# sketch_v1_01.net
KiCad netlist of a schematic drawn in EAGLE
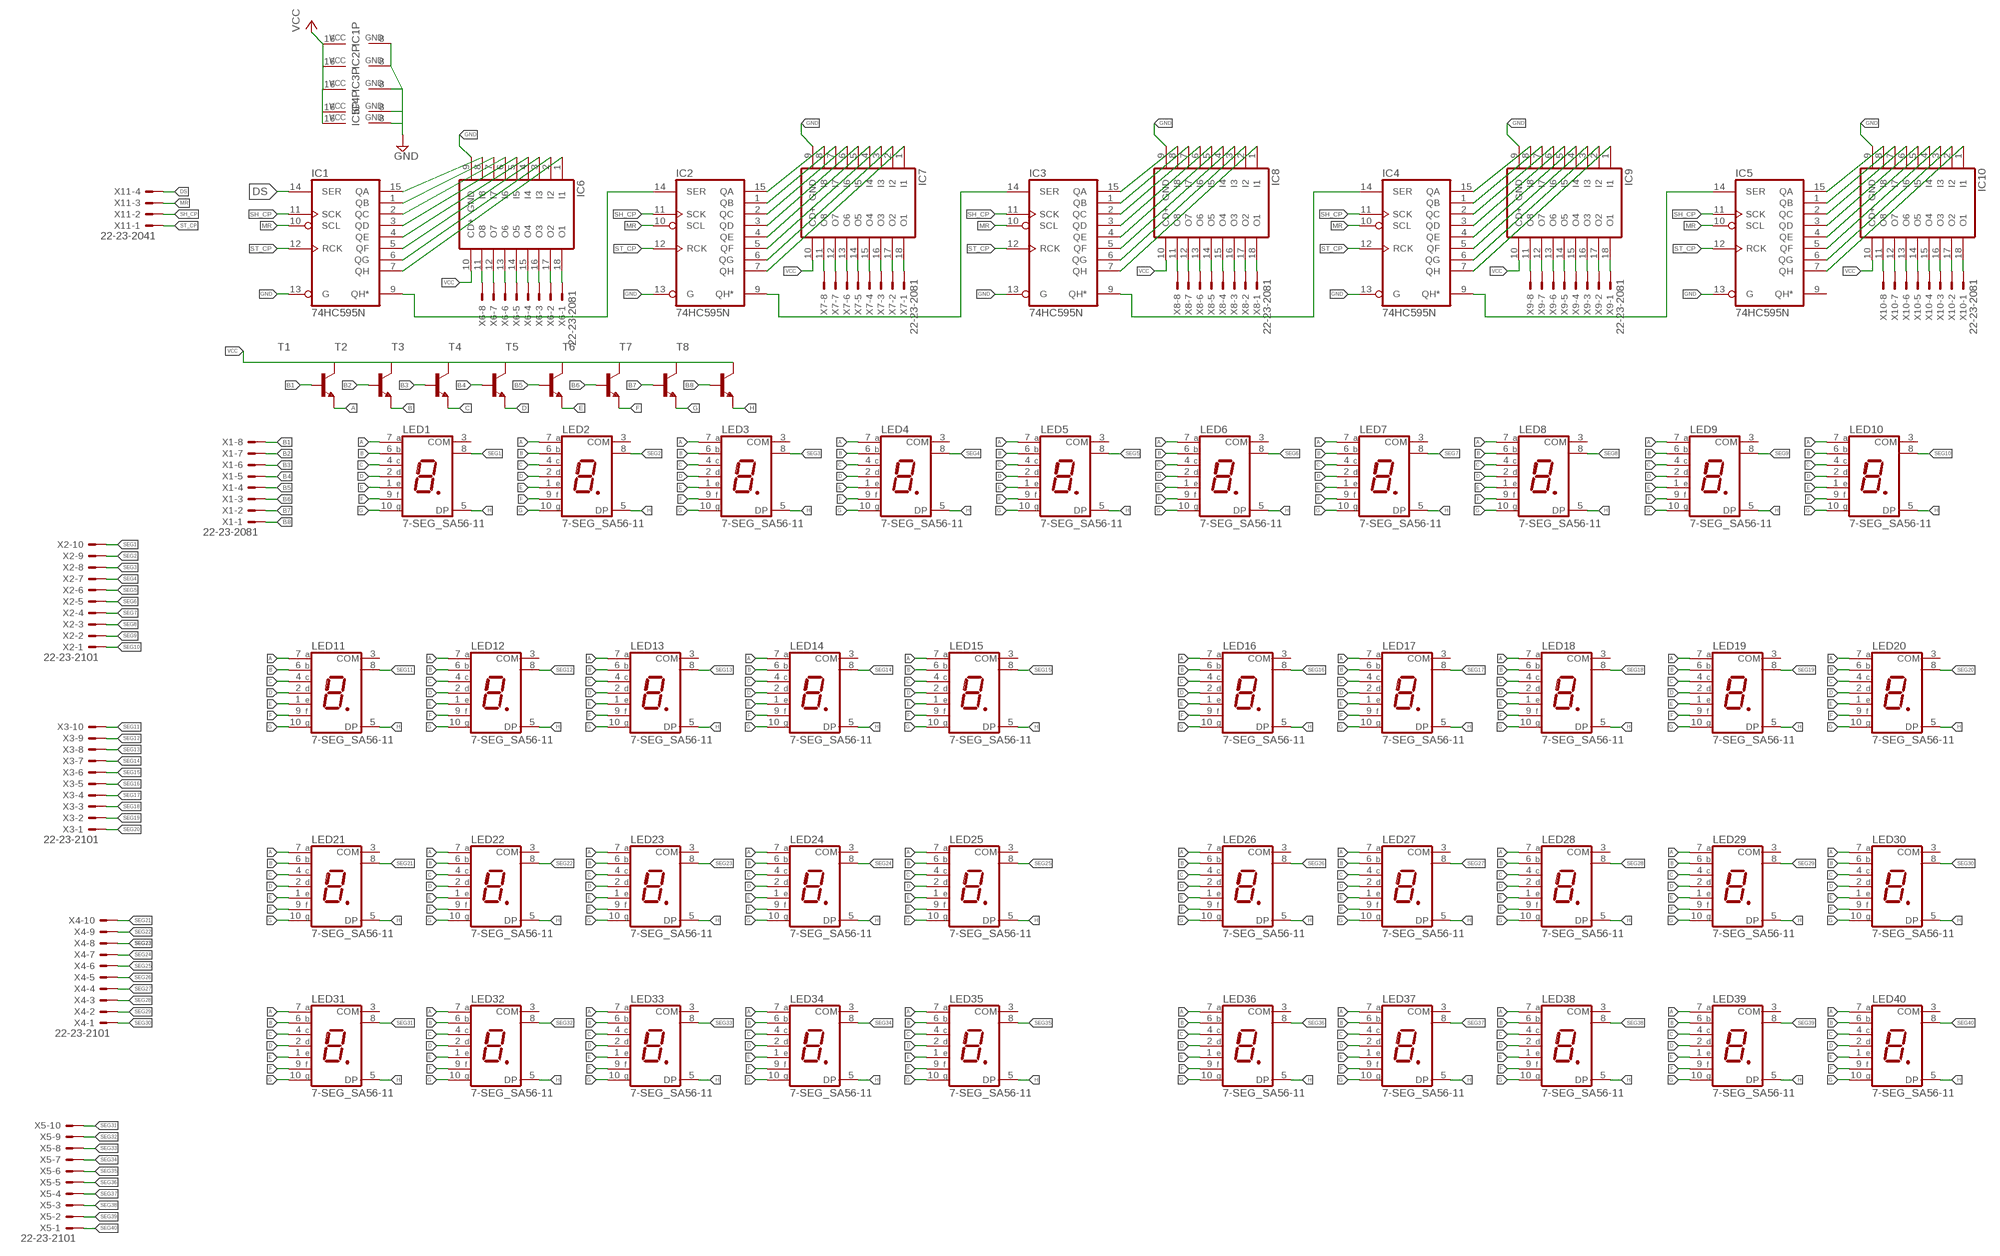
[diagram p0: schematic, sheet 1]

(export (version "E")
  (design (tool "Eeschema 10.0.6"))
  (components
    (comp (ref "IC1")
      (value "74HC595N")
      (footprint "eagle-import:DIL16")
      (libsource (lib "eagle-import") (part "74595NHC"))
    )
    (comp (ref "IC2")
      (value "74HC595N")
      (footprint "eagle-import:DIL16")
      (libsource (lib "eagle-import") (part "74595NHC"))
    )
    (comp (ref "IC3")
      (value "74HC595N")
      (footprint "eagle-import:DIL16")
      (libsource (lib "eagle-import") (part "74595NHC"))
    )
    (comp (ref "IC4")
      (value "74HC595N")
      (footprint "eagle-import:DIL16")
      (libsource (lib "eagle-import") (part "74595NHC"))
    )
    (comp (ref "IC5")
      (value "74HC595N")
      (footprint "eagle-import:DIL16")
      (libsource (lib "eagle-import") (part "74595NHC"))
    )
    (comp (ref "IC6")
      (value "ULN2803A")
      (footprint "eagle-import:DIL18")
      (libsource (lib "eagle-import") (part "ULN2803A"))
    )
    (comp (ref "IC7")
      (value "ULN2803A")
      (footprint "eagle-import:DIL18")
      (libsource (lib "eagle-import") (part "ULN2803A"))
    )
    (comp (ref "IC8")
      (value "ULN2803A")
      (footprint "eagle-import:DIL18")
      (libsource (lib "eagle-import") (part "ULN2803A"))
    )
    (comp (ref "IC9")
      (value "ULN2803A")
      (footprint "eagle-import:DIL18")
      (libsource (lib "eagle-import") (part "ULN2803A"))
    )
    (comp (ref "IC10")
      (value "ULN2803A")
      (footprint "eagle-import:DIL18")
      (libsource (lib "eagle-import") (part "ULN2803A"))
    )
    (comp (ref "LED1")
      (value "7-SEG_SA56-11")
      (footprint "eagle-import:SA56-11")
      (libsource (lib "eagle-import") (part "7-SEG_SA56-11"))
    )
    (comp (ref "LED2")
      (value "7-SEG_SA56-11")
      (footprint "eagle-import:SA56-11")
      (libsource (lib "eagle-import") (part "7-SEG_SA56-11"))
    )
    (comp (ref "LED3")
      (value "7-SEG_SA56-11")
      (footprint "eagle-import:SA56-11")
      (libsource (lib "eagle-import") (part "7-SEG_SA56-11"))
    )
    (comp (ref "LED4")
      (value "7-SEG_SA56-11")
      (footprint "eagle-import:SA56-11")
      (libsource (lib "eagle-import") (part "7-SEG_SA56-11"))
    )
    (comp (ref "LED5")
      (value "7-SEG_SA56-11")
      (footprint "eagle-import:SA56-11")
      (libsource (lib "eagle-import") (part "7-SEG_SA56-11"))
    )
    (comp (ref "LED6")
      (value "7-SEG_SA56-11")
      (footprint "eagle-import:SA56-11")
      (libsource (lib "eagle-import") (part "7-SEG_SA56-11"))
    )
    (comp (ref "LED7")
      (value "7-SEG_SA56-11")
      (footprint "eagle-import:SA56-11")
      (libsource (lib "eagle-import") (part "7-SEG_SA56-11"))
    )
    (comp (ref "LED8")
      (value "7-SEG_SA56-11")
      (footprint "eagle-import:SA56-11")
      (libsource (lib "eagle-import") (part "7-SEG_SA56-11"))
    )
    (comp (ref "LED9")
      (value "7-SEG_SA56-11")
      (footprint "eagle-import:SA56-11")
      (libsource (lib "eagle-import") (part "7-SEG_SA56-11"))
    )
    (comp (ref "LED10")
      (value "7-SEG_SA56-11")
      (footprint "eagle-import:SA56-11")
      (libsource (lib "eagle-import") (part "7-SEG_SA56-11"))
    )
    (comp (ref "LED11")
      (value "7-SEG_SA56-11")
      (footprint "eagle-import:SA56-11")
      (libsource (lib "eagle-import") (part "7-SEG_SA56-11"))
    )
    (comp (ref "LED12")
      (value "7-SEG_SA56-11")
      (footprint "eagle-import:SA56-11")
      (libsource (lib "eagle-import") (part "7-SEG_SA56-11"))
    )
    (comp (ref "LED13")
      (value "7-SEG_SA56-11")
      (footprint "eagle-import:SA56-11")
      (libsource (lib "eagle-import") (part "7-SEG_SA56-11"))
    )
    (comp (ref "LED14")
      (value "7-SEG_SA56-11")
      (footprint "eagle-import:SA56-11")
      (libsource (lib "eagle-import") (part "7-SEG_SA56-11"))
    )
    (comp (ref "LED15")
      (value "7-SEG_SA56-11")
      (footprint "eagle-import:SA56-11")
      (libsource (lib "eagle-import") (part "7-SEG_SA56-11"))
    )
    (comp (ref "LED16")
      (value "7-SEG_SA56-11")
      (footprint "eagle-import:SA56-11")
      (libsource (lib "eagle-import") (part "7-SEG_SA56-11"))
    )
    (comp (ref "LED17")
      (value "7-SEG_SA56-11")
      (footprint "eagle-import:SA56-11")
      (libsource (lib "eagle-import") (part "7-SEG_SA56-11"))
    )
    (comp (ref "LED18")
      (value "7-SEG_SA56-11")
      (footprint "eagle-import:SA56-11")
      (libsource (lib "eagle-import") (part "7-SEG_SA56-11"))
    )
    (comp (ref "LED19")
      (value "7-SEG_SA56-11")
      (footprint "eagle-import:SA56-11")
      (libsource (lib "eagle-import") (part "7-SEG_SA56-11"))
    )
    (comp (ref "LED20")
      (value "7-SEG_SA56-11")
      (footprint "eagle-import:SA56-11")
      (libsource (lib "eagle-import") (part "7-SEG_SA56-11"))
    )
    (comp (ref "LED21")
      (value "7-SEG_SA56-11")
      (footprint "eagle-import:SA56-11")
      (libsource (lib "eagle-import") (part "7-SEG_SA56-11"))
    )
    (comp (ref "LED22")
      (value "7-SEG_SA56-11")
      (footprint "eagle-import:SA56-11")
      (libsource (lib "eagle-import") (part "7-SEG_SA56-11"))
    )
    (comp (ref "LED23")
      (value "7-SEG_SA56-11")
      (footprint "eagle-import:SA56-11")
      (libsource (lib "eagle-import") (part "7-SEG_SA56-11"))
    )
    (comp (ref "LED24")
      (value "7-SEG_SA56-11")
      (footprint "eagle-import:SA56-11")
      (libsource (lib "eagle-import") (part "7-SEG_SA56-11"))
    )
    (comp (ref "LED25")
      (value "7-SEG_SA56-11")
      (footprint "eagle-import:SA56-11")
      (libsource (lib "eagle-import") (part "7-SEG_SA56-11"))
    )
    (comp (ref "LED26")
      (value "7-SEG_SA56-11")
      (footprint "eagle-import:SA56-11")
      (libsource (lib "eagle-import") (part "7-SEG_SA56-11"))
    )
    (comp (ref "LED27")
      (value "7-SEG_SA56-11")
      (footprint "eagle-import:SA56-11")
      (libsource (lib "eagle-import") (part "7-SEG_SA56-11"))
    )
    (comp (ref "LED28")
      (value "7-SEG_SA56-11")
      (footprint "eagle-import:SA56-11")
      (libsource (lib "eagle-import") (part "7-SEG_SA56-11"))
    )
    (comp (ref "LED29")
      (value "7-SEG_SA56-11")
      (footprint "eagle-import:SA56-11")
      (libsource (lib "eagle-import") (part "7-SEG_SA56-11"))
    )
    (comp (ref "LED30")
      (value "7-SEG_SA56-11")
      (footprint "eagle-import:SA56-11")
      (libsource (lib "eagle-import") (part "7-SEG_SA56-11"))
    )
    (comp (ref "LED31")
      (value "7-SEG_SA56-11")
      (footprint "eagle-import:SA56-11")
      (libsource (lib "eagle-import") (part "7-SEG_SA56-11"))
    )
    (comp (ref "LED32")
      (value "7-SEG_SA56-11")
      (footprint "eagle-import:SA56-11")
      (libsource (lib "eagle-import") (part "7-SEG_SA56-11"))
    )
    (comp (ref "LED33")
      (value "7-SEG_SA56-11")
      (footprint "eagle-import:SA56-11")
      (libsource (lib "eagle-import") (part "7-SEG_SA56-11"))
    )
    (comp (ref "LED34")
      (value "7-SEG_SA56-11")
      (footprint "eagle-import:SA56-11")
      (libsource (lib "eagle-import") (part "7-SEG_SA56-11"))
    )
    (comp (ref "LED35")
      (value "7-SEG_SA56-11")
      (footprint "eagle-import:SA56-11")
      (libsource (lib "eagle-import") (part "7-SEG_SA56-11"))
    )
    (comp (ref "LED36")
      (value "7-SEG_SA56-11")
      (footprint "eagle-import:SA56-11")
      (libsource (lib "eagle-import") (part "7-SEG_SA56-11"))
    )
    (comp (ref "LED37")
      (value "7-SEG_SA56-11")
      (footprint "eagle-import:SA56-11")
      (libsource (lib "eagle-import") (part "7-SEG_SA56-11"))
    )
    (comp (ref "LED38")
      (value "7-SEG_SA56-11")
      (footprint "eagle-import:SA56-11")
      (libsource (lib "eagle-import") (part "7-SEG_SA56-11"))
    )
    (comp (ref "LED39")
      (value "7-SEG_SA56-11")
      (footprint "eagle-import:SA56-11")
      (libsource (lib "eagle-import") (part "7-SEG_SA56-11"))
    )
    (comp (ref "LED40")
      (value "7-SEG_SA56-11")
      (footprint "eagle-import:SA56-11")
      (libsource (lib "eagle-import") (part "7-SEG_SA56-11"))
    )
    (comp (ref "T1")
      (value "-NPN-TO92")
      (footprint "eagle-import:TO92")
      (libsource (lib "eagle-import") (part "-NPN-TO92"))
    )
    (comp (ref "T2")
      (value "-NPN-TO92")
      (footprint "eagle-import:TO92")
      (libsource (lib "eagle-import") (part "-NPN-TO92"))
    )
    (comp (ref "T3")
      (value "-NPN-TO92")
      (footprint "eagle-import:TO92")
      (libsource (lib "eagle-import") (part "-NPN-TO92"))
    )
    (comp (ref "T4")
      (value "-NPN-TO92")
      (footprint "eagle-import:TO92")
      (libsource (lib "eagle-import") (part "-NPN-TO92"))
    )
    (comp (ref "T5")
      (value "-NPN-TO92")
      (footprint "eagle-import:TO92")
      (libsource (lib "eagle-import") (part "-NPN-TO92"))
    )
    (comp (ref "T6")
      (value "-NPN-TO92")
      (footprint "eagle-import:TO92")
      (libsource (lib "eagle-import") (part "-NPN-TO92"))
    )
    (comp (ref "T7")
      (value "-NPN-TO92")
      (footprint "eagle-import:TO92")
      (libsource (lib "eagle-import") (part "-NPN-TO92"))
    )
    (comp (ref "T8")
      (value "-NPN-TO92")
      (footprint "eagle-import:TO92")
      (libsource (lib "eagle-import") (part "-NPN-TO92"))
    )
    (comp (ref "X1")
      (value "22-23-2081")
      (footprint "eagle-import:22-23-2081")
      (fields (field (name "MF") "MOLEX"))
      (libsource (lib "eagle-import") (part "22-23-2081"))
    )
    (comp (ref "X2")
      (value "22-23-2101")
      (footprint "eagle-import:22-23-2101")
      (fields (field (name "MF") "MOLEX"))
      (libsource (lib "eagle-import") (part "22-23-2101"))
    )
    (comp (ref "X3")
      (value "22-23-2101")
      (footprint "eagle-import:22-23-2101")
      (fields (field (name "MF") "MOLEX"))
      (libsource (lib "eagle-import") (part "22-23-2101"))
    )
    (comp (ref "X4")
      (value "22-23-2101")
      (footprint "eagle-import:22-23-2101")
      (fields (field (name "MF") "MOLEX"))
      (libsource (lib "eagle-import") (part "22-23-2101"))
    )
    (comp (ref "X5")
      (value "22-23-2101")
      (footprint "eagle-import:22-23-2101")
      (fields (field (name "MF") "MOLEX"))
      (libsource (lib "eagle-import") (part "22-23-2101"))
    )
    (comp (ref "X6")
      (value "22-23-2081")
      (footprint "eagle-import:22-23-2081")
      (fields (field (name "MF") "MOLEX"))
      (libsource (lib "eagle-import") (part "22-23-2081"))
    )
    (comp (ref "X7")
      (value "22-23-2081")
      (footprint "eagle-import:22-23-2081")
      (fields (field (name "MF") "MOLEX"))
      (libsource (lib "eagle-import") (part "22-23-2081"))
    )
    (comp (ref "X8")
      (value "22-23-2081")
      (footprint "eagle-import:22-23-2081")
      (fields (field (name "MF") "MOLEX"))
      (libsource (lib "eagle-import") (part "22-23-2081"))
    )
    (comp (ref "X9")
      (value "22-23-2081")
      (footprint "eagle-import:22-23-2081")
      (fields (field (name "MF") "MOLEX"))
      (libsource (lib "eagle-import") (part "22-23-2081"))
    )
    (comp (ref "X10")
      (value "22-23-2081")
      (footprint "eagle-import:22-23-2081")
      (fields (field (name "MF") "MOLEX"))
      (libsource (lib "eagle-import") (part "22-23-2081"))
    )
    (comp (ref "X11")
      (value "22-23-2041")
      (footprint "eagle-import:22-23-2041")
      (fields (field (name "MF") "MOLEX"))
      (libsource (lib "eagle-import") (part "22-23-2041"))
    )
  )
  (nets
    (net (code "1") (name "A") (class "Default")
      (node (ref "LED1") (pin "7") (pinfunction "A_7") (pintype "passive"))
      (node (ref "LED10") (pin "7") (pinfunction "A_7") (pintype "passive"))
      (node (ref "LED11") (pin "7") (pinfunction "A_7") (pintype "passive"))
      (node (ref "LED12") (pin "7") (pinfunction "A_7") (pintype "passive"))
      (node (ref "LED13") (pin "7") (pinfunction "A_7") (pintype "passive"))
      (node (ref "LED14") (pin "7") (pinfunction "A_7") (pintype "passive"))
      (node (ref "LED15") (pin "7") (pinfunction "A_7") (pintype "passive"))
      (node (ref "LED16") (pin "7") (pinfunction "A_7") (pintype "passive"))
      (node (ref "LED17") (pin "7") (pinfunction "A_7") (pintype "passive"))
      (node (ref "LED18") (pin "7") (pinfunction "A_7") (pintype "passive"))
      (node (ref "LED19") (pin "7") (pinfunction "A_7") (pintype "passive"))
      (node (ref "LED2") (pin "7") (pinfunction "A_7") (pintype "passive"))
      (node (ref "LED20") (pin "7") (pinfunction "A_7") (pintype "passive"))
      (node (ref "LED21") (pin "7") (pinfunction "A_7") (pintype "passive"))
      (node (ref "LED22") (pin "7") (pinfunction "A_7") (pintype "passive"))
      (node (ref "LED23") (pin "7") (pinfunction "A_7") (pintype "passive"))
      (node (ref "LED24") (pin "7") (pinfunction "A_7") (pintype "passive"))
      (node (ref "LED25") (pin "7") (pinfunction "A_7") (pintype "passive"))
      (node (ref "LED26") (pin "7") (pinfunction "A_7") (pintype "passive"))
      (node (ref "LED27") (pin "7") (pinfunction "A_7") (pintype "passive"))
      (node (ref "LED28") (pin "7") (pinfunction "A_7") (pintype "passive"))
      (node (ref "LED29") (pin "7") (pinfunction "A_7") (pintype "passive"))
      (node (ref "LED3") (pin "7") (pinfunction "A_7") (pintype "passive"))
      (node (ref "LED30") (pin "7") (pinfunction "A_7") (pintype "passive"))
      (node (ref "LED31") (pin "7") (pinfunction "A_7") (pintype "passive"))
      (node (ref "LED32") (pin "7") (pinfunction "A_7") (pintype "passive"))
      (node (ref "LED33") (pin "7") (pinfunction "A_7") (pintype "passive"))
      (node (ref "LED34") (pin "7") (pinfunction "A_7") (pintype "passive"))
      (node (ref "LED35") (pin "7") (pinfunction "A_7") (pintype "passive"))
      (node (ref "LED36") (pin "7") (pinfunction "A_7") (pintype "passive"))
      (node (ref "LED37") (pin "7") (pinfunction "A_7") (pintype "passive"))
      (node (ref "LED38") (pin "7") (pinfunction "A_7") (pintype "passive"))
      (node (ref "LED39") (pin "7") (pinfunction "A_7") (pintype "passive"))
      (node (ref "LED4") (pin "7") (pinfunction "A_7") (pintype "passive"))
      (node (ref "LED40") (pin "7") (pinfunction "A_7") (pintype "passive"))
      (node (ref "LED5") (pin "7") (pinfunction "A_7") (pintype "passive"))
      (node (ref "LED6") (pin "7") (pinfunction "A_7") (pintype "passive"))
      (node (ref "LED7") (pin "7") (pinfunction "A_7") (pintype "passive"))
      (node (ref "LED8") (pin "7") (pinfunction "A_7") (pintype "passive"))
      (node (ref "LED9") (pin "7") (pinfunction "A_7") (pintype "passive"))
      (node (ref "T1") (pin "1") (pinfunction "E_1") (pintype "passive"))
    )
    (net (code "2") (name "B") (class "Default")
      (node (ref "LED1") (pin "6") (pinfunction "B_6") (pintype "passive"))
      (node (ref "LED10") (pin "6") (pinfunction "B_6") (pintype "passive"))
      (node (ref "LED11") (pin "6") (pinfunction "B_6") (pintype "passive"))
      (node (ref "LED12") (pin "6") (pinfunction "B_6") (pintype "passive"))
      (node (ref "LED13") (pin "6") (pinfunction "B_6") (pintype "passive"))
      (node (ref "LED14") (pin "6") (pinfunction "B_6") (pintype "passive"))
      (node (ref "LED15") (pin "6") (pinfunction "B_6") (pintype "passive"))
      (node (ref "LED16") (pin "6") (pinfunction "B_6") (pintype "passive"))
      (node (ref "LED17") (pin "6") (pinfunction "B_6") (pintype "passive"))
      (node (ref "LED18") (pin "6") (pinfunction "B_6") (pintype "passive"))
      (node (ref "LED19") (pin "6") (pinfunction "B_6") (pintype "passive"))
      (node (ref "LED2") (pin "6") (pinfunction "B_6") (pintype "passive"))
      (node (ref "LED20") (pin "6") (pinfunction "B_6") (pintype "passive"))
      (node (ref "LED21") (pin "6") (pinfunction "B_6") (pintype "passive"))
      (node (ref "LED22") (pin "6") (pinfunction "B_6") (pintype "passive"))
      (node (ref "LED23") (pin "6") (pinfunction "B_6") (pintype "passive"))
      (node (ref "LED24") (pin "6") (pinfunction "B_6") (pintype "passive"))
      (node (ref "LED25") (pin "6") (pinfunction "B_6") (pintype "passive"))
      (node (ref "LED26") (pin "6") (pinfunction "B_6") (pintype "passive"))
      (node (ref "LED27") (pin "6") (pinfunction "B_6") (pintype "passive"))
      (node (ref "LED28") (pin "6") (pinfunction "B_6") (pintype "passive"))
      (node (ref "LED29") (pin "6") (pinfunction "B_6") (pintype "passive"))
      (node (ref "LED3") (pin "6") (pinfunction "B_6") (pintype "passive"))
      (node (ref "LED30") (pin "6") (pinfunction "B_6") (pintype "passive"))
      (node (ref "LED31") (pin "6") (pinfunction "B_6") (pintype "passive"))
      (node (ref "LED32") (pin "6") (pinfunction "B_6") (pintype "passive"))
      (node (ref "LED33") (pin "6") (pinfunction "B_6") (pintype "passive"))
      (node (ref "LED34") (pin "6") (pinfunction "B_6") (pintype "passive"))
      (node (ref "LED35") (pin "6") (pinfunction "B_6") (pintype "passive"))
      (node (ref "LED36") (pin "6") (pinfunction "B_6") (pintype "passive"))
      (node (ref "LED37") (pin "6") (pinfunction "B_6") (pintype "passive"))
      (node (ref "LED38") (pin "6") (pinfunction "B_6") (pintype "passive"))
      (node (ref "LED39") (pin "6") (pinfunction "B_6") (pintype "passive"))
      (node (ref "LED4") (pin "6") (pinfunction "B_6") (pintype "passive"))
      (node (ref "LED40") (pin "6") (pinfunction "B_6") (pintype "passive"))
      (node (ref "LED5") (pin "6") (pinfunction "B_6") (pintype "passive"))
      (node (ref "LED6") (pin "6") (pinfunction "B_6") (pintype "passive"))
      (node (ref "LED7") (pin "6") (pinfunction "B_6") (pintype "passive"))
      (node (ref "LED8") (pin "6") (pinfunction "B_6") (pintype "passive"))
      (node (ref "LED9") (pin "6") (pinfunction "B_6") (pintype "passive"))
      (node (ref "T2") (pin "1") (pinfunction "E_1") (pintype "passive"))
    )
    (net (code "3") (name "B1") (class "Default")
      (node (ref "T1") (pin "2") (pinfunction "B_2") (pintype "passive"))
      (node (ref "X1") (pin "8") (pinfunction "S_8") (pintype "passive"))
    )
    (net (code "4") (name "B2") (class "Default")
      (node (ref "T2") (pin "2") (pinfunction "B_2") (pintype "passive"))
      (node (ref "X1") (pin "7") (pinfunction "S_7") (pintype "passive"))
    )
    (net (code "5") (name "B3") (class "Default")
      (node (ref "T3") (pin "2") (pinfunction "B_2") (pintype "passive"))
      (node (ref "X1") (pin "6") (pinfunction "S_6") (pintype "passive"))
    )
    (net (code "6") (name "B4") (class "Default")
      (node (ref "T4") (pin "2") (pinfunction "B_2") (pintype "passive"))
      (node (ref "X1") (pin "5") (pinfunction "S_5") (pintype "passive"))
    )
    (net (code "7") (name "B5") (class "Default")
      (node (ref "T5") (pin "2") (pinfunction "B_2") (pintype "passive"))
      (node (ref "X1") (pin "4") (pinfunction "S_4") (pintype "passive"))
    )
    (net (code "8") (name "B6") (class "Default")
      (node (ref "T6") (pin "2") (pinfunction "B_2") (pintype "passive"))
      (node (ref "X1") (pin "3") (pinfunction "S_3") (pintype "passive"))
    )
    (net (code "9") (name "B7") (class "Default")
      (node (ref "T7") (pin "2") (pinfunction "B_2") (pintype "passive"))
      (node (ref "X1") (pin "2") (pinfunction "S_2") (pintype "passive"))
    )
    (net (code "10") (name "B8") (class "Default")
      (node (ref "T8") (pin "2") (pinfunction "B_2") (pintype "passive"))
      (node (ref "X1") (pin "1") (pinfunction "S_1") (pintype "passive"))
    )
    (net (code "11") (name "C") (class "Default")
      (node (ref "LED1") (pin "4") (pinfunction "C_4") (pintype "passive"))
      (node (ref "LED10") (pin "4") (pinfunction "C_4") (pintype "passive"))
      (node (ref "LED11") (pin "4") (pinfunction "C_4") (pintype "passive"))
      (node (ref "LED12") (pin "4") (pinfunction "C_4") (pintype "passive"))
      (node (ref "LED13") (pin "4") (pinfunction "C_4") (pintype "passive"))
      (node (ref "LED14") (pin "4") (pinfunction "C_4") (pintype "passive"))
      (node (ref "LED15") (pin "4") (pinfunction "C_4") (pintype "passive"))
      (node (ref "LED16") (pin "4") (pinfunction "C_4") (pintype "passive"))
      (node (ref "LED17") (pin "4") (pinfunction "C_4") (pintype "passive"))
      (node (ref "LED18") (pin "4") (pinfunction "C_4") (pintype "passive"))
      (node (ref "LED19") (pin "4") (pinfunction "C_4") (pintype "passive"))
      (node (ref "LED2") (pin "4") (pinfunction "C_4") (pintype "passive"))
      (node (ref "LED20") (pin "4") (pinfunction "C_4") (pintype "passive"))
      (node (ref "LED21") (pin "4") (pinfunction "C_4") (pintype "passive"))
      (node (ref "LED22") (pin "4") (pinfunction "C_4") (pintype "passive"))
      (node (ref "LED23") (pin "4") (pinfunction "C_4") (pintype "passive"))
      (node (ref "LED24") (pin "4") (pinfunction "C_4") (pintype "passive"))
      (node (ref "LED25") (pin "4") (pinfunction "C_4") (pintype "passive"))
      (node (ref "LED26") (pin "4") (pinfunction "C_4") (pintype "passive"))
      (node (ref "LED27") (pin "4") (pinfunction "C_4") (pintype "passive"))
      (node (ref "LED28") (pin "4") (pinfunction "C_4") (pintype "passive"))
      (node (ref "LED29") (pin "4") (pinfunction "C_4") (pintype "passive"))
      (node (ref "LED3") (pin "4") (pinfunction "C_4") (pintype "passive"))
      (node (ref "LED30") (pin "4") (pinfunction "C_4") (pintype "passive"))
      (node (ref "LED31") (pin "4") (pinfunction "C_4") (pintype "passive"))
      (node (ref "LED32") (pin "4") (pinfunction "C_4") (pintype "passive"))
      (node (ref "LED33") (pin "4") (pinfunction "C_4") (pintype "passive"))
      (node (ref "LED34") (pin "4") (pinfunction "C_4") (pintype "passive"))
      (node (ref "LED35") (pin "4") (pinfunction "C_4") (pintype "passive"))
      (node (ref "LED36") (pin "4") (pinfunction "C_4") (pintype "passive"))
      (node (ref "LED37") (pin "4") (pinfunction "C_4") (pintype "passive"))
      (node (ref "LED38") (pin "4") (pinfunction "C_4") (pintype "passive"))
      (node (ref "LED39") (pin "4") (pinfunction "C_4") (pintype "passive"))
      (node (ref "LED4") (pin "4") (pinfunction "C_4") (pintype "passive"))
      (node (ref "LED40") (pin "4") (pinfunction "C_4") (pintype "passive"))
      (node (ref "LED5") (pin "4") (pinfunction "C_4") (pintype "passive"))
      (node (ref "LED6") (pin "4") (pinfunction "C_4") (pintype "passive"))
      (node (ref "LED7") (pin "4") (pinfunction "C_4") (pintype "passive"))
      (node (ref "LED8") (pin "4") (pinfunction "C_4") (pintype "passive"))
      (node (ref "LED9") (pin "4") (pinfunction "C_4") (pintype "passive"))
      (node (ref "T3") (pin "1") (pinfunction "E_1") (pintype "passive"))
    )
    (net (code "12") (name "D") (class "Default")
      (node (ref "LED1") (pin "2") (pinfunction "D_2") (pintype "passive"))
      (node (ref "LED10") (pin "2") (pinfunction "D_2") (pintype "passive"))
      (node (ref "LED11") (pin "2") (pinfunction "D_2") (pintype "passive"))
      (node (ref "LED12") (pin "2") (pinfunction "D_2") (pintype "passive"))
      (node (ref "LED13") (pin "2") (pinfunction "D_2") (pintype "passive"))
      (node (ref "LED14") (pin "2") (pinfunction "D_2") (pintype "passive"))
      (node (ref "LED15") (pin "2") (pinfunction "D_2") (pintype "passive"))
      (node (ref "LED16") (pin "2") (pinfunction "D_2") (pintype "passive"))
      (node (ref "LED17") (pin "2") (pinfunction "D_2") (pintype "passive"))
      (node (ref "LED18") (pin "2") (pinfunction "D_2") (pintype "passive"))
      (node (ref "LED19") (pin "2") (pinfunction "D_2") (pintype "passive"))
      (node (ref "LED2") (pin "2") (pinfunction "D_2") (pintype "passive"))
      (node (ref "LED20") (pin "2") (pinfunction "D_2") (pintype "passive"))
      (node (ref "LED21") (pin "2") (pinfunction "D_2") (pintype "passive"))
      (node (ref "LED22") (pin "2") (pinfunction "D_2") (pintype "passive"))
      (node (ref "LED23") (pin "2") (pinfunction "D_2") (pintype "passive"))
      (node (ref "LED24") (pin "2") (pinfunction "D_2") (pintype "passive"))
      (node (ref "LED25") (pin "2") (pinfunction "D_2") (pintype "passive"))
      (node (ref "LED26") (pin "2") (pinfunction "D_2") (pintype "passive"))
      (node (ref "LED27") (pin "2") (pinfunction "D_2") (pintype "passive"))
      (node (ref "LED28") (pin "2") (pinfunction "D_2") (pintype "passive"))
      (node (ref "LED29") (pin "2") (pinfunction "D_2") (pintype "passive"))
      (node (ref "LED3") (pin "2") (pinfunction "D_2") (pintype "passive"))
      (node (ref "LED30") (pin "2") (pinfunction "D_2") (pintype "passive"))
      (node (ref "LED31") (pin "2") (pinfunction "D_2") (pintype "passive"))
      (node (ref "LED32") (pin "2") (pinfunction "D_2") (pintype "passive"))
      (node (ref "LED33") (pin "2") (pinfunction "D_2") (pintype "passive"))
      (node (ref "LED34") (pin "2") (pinfunction "D_2") (pintype "passive"))
      (node (ref "LED35") (pin "2") (pinfunction "D_2") (pintype "passive"))
      (node (ref "LED36") (pin "2") (pinfunction "D_2") (pintype "passive"))
      (node (ref "LED37") (pin "2") (pinfunction "D_2") (pintype "passive"))
      (node (ref "LED38") (pin "2") (pinfunction "D_2") (pintype "passive"))
      (node (ref "LED39") (pin "2") (pinfunction "D_2") (pintype "passive"))
      (node (ref "LED4") (pin "2") (pinfunction "D_2") (pintype "passive"))
      (node (ref "LED40") (pin "2") (pinfunction "D_2") (pintype "passive"))
      (node (ref "LED5") (pin "2") (pinfunction "D_2") (pintype "passive"))
      (node (ref "LED6") (pin "2") (pinfunction "D_2") (pintype "passive"))
      (node (ref "LED7") (pin "2") (pinfunction "D_2") (pintype "passive"))
      (node (ref "LED8") (pin "2") (pinfunction "D_2") (pintype "passive"))
      (node (ref "LED9") (pin "2") (pinfunction "D_2") (pintype "passive"))
      (node (ref "T4") (pin "1") (pinfunction "E_1") (pintype "passive"))
    )
    (net (code "13") (name "DS") (class "Default")
      (node (ref "IC1") (pin "14") (pinfunction "SER_14") (pintype "input"))
      (node (ref "X11") (pin "4") (pinfunction "S_4") (pintype "passive"))
    )
    (net (code "14") (name "E") (class "Default")
      (node (ref "LED1") (pin "1") (pinfunction "E_1") (pintype "passive"))
      (node (ref "LED10") (pin "1") (pinfunction "E_1") (pintype "passive"))
      (node (ref "LED11") (pin "1") (pinfunction "E_1") (pintype "passive"))
      (node (ref "LED12") (pin "1") (pinfunction "E_1") (pintype "passive"))
      (node (ref "LED13") (pin "1") (pinfunction "E_1") (pintype "passive"))
      (node (ref "LED14") (pin "1") (pinfunction "E_1") (pintype "passive"))
      (node (ref "LED15") (pin "1") (pinfunction "E_1") (pintype "passive"))
      (node (ref "LED16") (pin "1") (pinfunction "E_1") (pintype "passive"))
      (node (ref "LED17") (pin "1") (pinfunction "E_1") (pintype "passive"))
      (node (ref "LED18") (pin "1") (pinfunction "E_1") (pintype "passive"))
      (node (ref "LED19") (pin "1") (pinfunction "E_1") (pintype "passive"))
      (node (ref "LED2") (pin "1") (pinfunction "E_1") (pintype "passive"))
      (node (ref "LED20") (pin "1") (pinfunction "E_1") (pintype "passive"))
      (node (ref "LED21") (pin "1") (pinfunction "E_1") (pintype "passive"))
      (node (ref "LED22") (pin "1") (pinfunction "E_1") (pintype "passive"))
      (node (ref "LED23") (pin "1") (pinfunction "E_1") (pintype "passive"))
      (node (ref "LED24") (pin "1") (pinfunction "E_1") (pintype "passive"))
      (node (ref "LED25") (pin "1") (pinfunction "E_1") (pintype "passive"))
      (node (ref "LED26") (pin "1") (pinfunction "E_1") (pintype "passive"))
      (node (ref "LED27") (pin "1") (pinfunction "E_1") (pintype "passive"))
      (node (ref "LED28") (pin "1") (pinfunction "E_1") (pintype "passive"))
      (node (ref "LED29") (pin "1") (pinfunction "E_1") (pintype "passive"))
      (node (ref "LED3") (pin "1") (pinfunction "E_1") (pintype "passive"))
      (node (ref "LED30") (pin "1") (pinfunction "E_1") (pintype "passive"))
      (node (ref "LED31") (pin "1") (pinfunction "E_1") (pintype "passive"))
      (node (ref "LED32") (pin "1") (pinfunction "E_1") (pintype "passive"))
      (node (ref "LED33") (pin "1") (pinfunction "E_1") (pintype "passive"))
      (node (ref "LED34") (pin "1") (pinfunction "E_1") (pintype "passive"))
      (node (ref "LED35") (pin "1") (pinfunction "E_1") (pintype "passive"))
      (node (ref "LED36") (pin "1") (pinfunction "E_1") (pintype "passive"))
      (node (ref "LED37") (pin "1") (pinfunction "E_1") (pintype "passive"))
      (node (ref "LED38") (pin "1") (pinfunction "E_1") (pintype "passive"))
      (node (ref "LED39") (pin "1") (pinfunction "E_1") (pintype "passive"))
      (node (ref "LED4") (pin "1") (pinfunction "E_1") (pintype "passive"))
      (node (ref "LED40") (pin "1") (pinfunction "E_1") (pintype "passive"))
      (node (ref "LED5") (pin "1") (pinfunction "E_1") (pintype "passive"))
      (node (ref "LED6") (pin "1") (pinfunction "E_1") (pintype "passive"))
      (node (ref "LED7") (pin "1") (pinfunction "E_1") (pintype "passive"))
      (node (ref "LED8") (pin "1") (pinfunction "E_1") (pintype "passive"))
      (node (ref "LED9") (pin "1") (pinfunction "E_1") (pintype "passive"))
      (node (ref "T5") (pin "1") (pinfunction "E_1") (pintype "passive"))
    )
    (net (code "15") (name "F") (class "Default")
      (node (ref "LED1") (pin "9") (pinfunction "F_9") (pintype "passive"))
      (node (ref "LED10") (pin "9") (pinfunction "F_9") (pintype "passive"))
      (node (ref "LED11") (pin "9") (pinfunction "F_9") (pintype "passive"))
      (node (ref "LED12") (pin "9") (pinfunction "F_9") (pintype "passive"))
      (node (ref "LED13") (pin "9") (pinfunction "F_9") (pintype "passive"))
      (node (ref "LED14") (pin "9") (pinfunction "F_9") (pintype "passive"))
      (node (ref "LED15") (pin "9") (pinfunction "F_9") (pintype "passive"))
      (node (ref "LED16") (pin "9") (pinfunction "F_9") (pintype "passive"))
      (node (ref "LED17") (pin "9") (pinfunction "F_9") (pintype "passive"))
      (node (ref "LED18") (pin "9") (pinfunction "F_9") (pintype "passive"))
      (node (ref "LED19") (pin "9") (pinfunction "F_9") (pintype "passive"))
      (node (ref "LED2") (pin "9") (pinfunction "F_9") (pintype "passive"))
      (node (ref "LED20") (pin "9") (pinfunction "F_9") (pintype "passive"))
      (node (ref "LED21") (pin "9") (pinfunction "F_9") (pintype "passive"))
      (node (ref "LED22") (pin "9") (pinfunction "F_9") (pintype "passive"))
      (node (ref "LED23") (pin "9") (pinfunction "F_9") (pintype "passive"))
      (node (ref "LED24") (pin "9") (pinfunction "F_9") (pintype "passive"))
      (node (ref "LED25") (pin "9") (pinfunction "F_9") (pintype "passive"))
      (node (ref "LED26") (pin "9") (pinfunction "F_9") (pintype "passive"))
      (node (ref "LED27") (pin "9") (pinfunction "F_9") (pintype "passive"))
      (node (ref "LED28") (pin "9") (pinfunction "F_9") (pintype "passive"))
      (node (ref "LED29") (pin "9") (pinfunction "F_9") (pintype "passive"))
      (node (ref "LED3") (pin "9") (pinfunction "F_9") (pintype "passive"))
      (node (ref "LED30") (pin "9") (pinfunction "F_9") (pintype "passive"))
      (node (ref "LED31") (pin "9") (pinfunction "F_9") (pintype "passive"))
      (node (ref "LED32") (pin "9") (pinfunction "F_9") (pintype "passive"))
      (node (ref "LED33") (pin "9") (pinfunction "F_9") (pintype "passive"))
      (node (ref "LED34") (pin "9") (pinfunction "F_9") (pintype "passive"))
      (node (ref "LED35") (pin "9") (pinfunction "F_9") (pintype "passive"))
      (node (ref "LED36") (pin "9") (pinfunction "F_9") (pintype "passive"))
      (node (ref "LED37") (pin "9") (pinfunction "F_9") (pintype "passive"))
      (node (ref "LED38") (pin "9") (pinfunction "F_9") (pintype "passive"))
      (node (ref "LED39") (pin "9") (pinfunction "F_9") (pintype "passive"))
      (node (ref "LED4") (pin "9") (pinfunction "F_9") (pintype "passive"))
      (node (ref "LED40") (pin "9") (pinfunction "F_9") (pintype "passive"))
      (node (ref "LED5") (pin "9") (pinfunction "F_9") (pintype "passive"))
      (node (ref "LED6") (pin "9") (pinfunction "F_9") (pintype "passive"))
      (node (ref "LED7") (pin "9") (pinfunction "F_9") (pintype "passive"))
      (node (ref "LED8") (pin "9") (pinfunction "F_9") (pintype "passive"))
      (node (ref "LED9") (pin "9") (pinfunction "F_9") (pintype "passive"))
      (node (ref "T6") (pin "1") (pinfunction "E_1") (pintype "passive"))
    )
    (net (code "16") (name "G") (class "Default")
      (node (ref "LED1") (pin "10") (pinfunction "G_10") (pintype "passive"))
      (node (ref "LED10") (pin "10") (pinfunction "G_10") (pintype "passive"))
      (node (ref "LED11") (pin "10") (pinfunction "G_10") (pintype "passive"))
      (node (ref "LED12") (pin "10") (pinfunction "G_10") (pintype "passive"))
      (node (ref "LED13") (pin "10") (pinfunction "G_10") (pintype "passive"))
      (node (ref "LED14") (pin "10") (pinfunction "G_10") (pintype "passive"))
      (node (ref "LED15") (pin "10") (pinfunction "G_10") (pintype "passive"))
      (node (ref "LED16") (pin "10") (pinfunction "G_10") (pintype "passive"))
      (node (ref "LED17") (pin "10") (pinfunction "G_10") (pintype "passive"))
      (node (ref "LED18") (pin "10") (pinfunction "G_10") (pintype "passive"))
      (node (ref "LED19") (pin "10") (pinfunction "G_10") (pintype "passive"))
      (node (ref "LED2") (pin "10") (pinfunction "G_10") (pintype "passive"))
      (node (ref "LED20") (pin "10") (pinfunction "G_10") (pintype "passive"))
      (node (ref "LED21") (pin "10") (pinfunction "G_10") (pintype "passive"))
      (node (ref "LED22") (pin "10") (pinfunction "G_10") (pintype "passive"))
      (node (ref "LED23") (pin "10") (pinfunction "G_10") (pintype "passive"))
      (node (ref "LED24") (pin "10") (pinfunction "G_10") (pintype "passive"))
      (node (ref "LED25") (pin "10") (pinfunction "G_10") (pintype "passive"))
      (node (ref "LED26") (pin "10") (pinfunction "G_10") (pintype "passive"))
      (node (ref "LED27") (pin "10") (pinfunction "G_10") (pintype "passive"))
      (node (ref "LED28") (pin "10") (pinfunction "G_10") (pintype "passive"))
      (node (ref "LED29") (pin "10") (pinfunction "G_10") (pintype "passive"))
      (node (ref "LED3") (pin "10") (pinfunction "G_10") (pintype "passive"))
      (node (ref "LED30") (pin "10") (pinfunction "G_10") (pintype "passive"))
      (node (ref "LED31") (pin "10") (pinfunction "G_10") (pintype "passive"))
      (node (ref "LED32") (pin "10") (pinfunction "G_10") (pintype "passive"))
      (node (ref "LED33") (pin "10") (pinfunction "G_10") (pintype "passive"))
      (node (ref "LED34") (pin "10") (pinfunction "G_10") (pintype "passive"))
      (node (ref "LED35") (pin "10") (pinfunction "G_10") (pintype "passive"))
      (node (ref "LED36") (pin "10") (pinfunction "G_10") (pintype "passive"))
      (node (ref "LED37") (pin "10") (pinfunction "G_10") (pintype "passive"))
      (node (ref "LED38") (pin "10") (pinfunction "G_10") (pintype "passive"))
      (node (ref "LED39") (pin "10") (pinfunction "G_10") (pintype "passive"))
      (node (ref "LED4") (pin "10") (pinfunction "G_10") (pintype "passive"))
      (node (ref "LED40") (pin "10") (pinfunction "G_10") (pintype "passive"))
      (node (ref "LED5") (pin "10") (pinfunction "G_10") (pintype "passive"))
      (node (ref "LED6") (pin "10") (pinfunction "G_10") (pintype "passive"))
      (node (ref "LED7") (pin "10") (pinfunction "G_10") (pintype "passive"))
      (node (ref "LED8") (pin "10") (pinfunction "G_10") (pintype "passive"))
      (node (ref "LED9") (pin "10") (pinfunction "G_10") (pintype "passive"))
      (node (ref "T7") (pin "1") (pinfunction "E_1") (pintype "passive"))
    )
    (net (code "17") (name "GND") (class "Default")
      (node (ref "IC1") (pin "13") (pinfunction "G_13") (pintype "input"))
      (node (ref "IC1") (pin "8") (pinfunction "GND_8") (pintype "power_in"))
      (node (ref "IC10") (pin "9") (pinfunction "GND_9") (pintype "power_in"))
      (node (ref "IC2") (pin "13") (pinfunction "G_13") (pintype "input"))
      (node (ref "IC2") (pin "8") (pinfunction "GND_8") (pintype "power_in"))
      (node (ref "IC3") (pin "13") (pinfunction "G_13") (pintype "input"))
      (node (ref "IC3") (pin "8") (pinfunction "GND_8") (pintype "power_in"))
      (node (ref "IC4") (pin "13") (pinfunction "G_13") (pintype "input"))
      (node (ref "IC4") (pin "8") (pinfunction "GND_8") (pintype "power_in"))
      (node (ref "IC5") (pin "13") (pinfunction "G_13") (pintype "input"))
      (node (ref "IC5") (pin "8") (pinfunction "GND_8") (pintype "power_in"))
      (node (ref "IC6") (pin "9") (pinfunction "GND_9") (pintype "power_in"))
      (node (ref "IC7") (pin "9") (pinfunction "GND_9") (pintype "power_in"))
      (node (ref "IC8") (pin "9") (pinfunction "GND_9") (pintype "power_in"))
      (node (ref "IC9") (pin "9") (pinfunction "GND_9") (pintype "power_in"))
    )
    (net (code "18") (name "H") (class "Default")
      (node (ref "LED1") (pin "5") (pinfunction "DP_5") (pintype "passive"))
      (node (ref "LED10") (pin "5") (pinfunction "DP_5") (pintype "passive"))
      (node (ref "LED11") (pin "5") (pinfunction "DP_5") (pintype "passive"))
      (node (ref "LED12") (pin "5") (pinfunction "DP_5") (pintype "passive"))
      (node (ref "LED13") (pin "5") (pinfunction "DP_5") (pintype "passive"))
      (node (ref "LED14") (pin "5") (pinfunction "DP_5") (pintype "passive"))
      (node (ref "LED15") (pin "5") (pinfunction "DP_5") (pintype "passive"))
      (node (ref "LED16") (pin "5") (pinfunction "DP_5") (pintype "passive"))
      (node (ref "LED17") (pin "5") (pinfunction "DP_5") (pintype "passive"))
      (node (ref "LED18") (pin "5") (pinfunction "DP_5") (pintype "passive"))
      (node (ref "LED19") (pin "5") (pinfunction "DP_5") (pintype "passive"))
      (node (ref "LED2") (pin "5") (pinfunction "DP_5") (pintype "passive"))
      (node (ref "LED20") (pin "5") (pinfunction "DP_5") (pintype "passive"))
      (node (ref "LED21") (pin "5") (pinfunction "DP_5") (pintype "passive"))
      (node (ref "LED22") (pin "5") (pinfunction "DP_5") (pintype "passive"))
      (node (ref "LED23") (pin "5") (pinfunction "DP_5") (pintype "passive"))
      (node (ref "LED24") (pin "5") (pinfunction "DP_5") (pintype "passive"))
      (node (ref "LED25") (pin "5") (pinfunction "DP_5") (pintype "passive"))
      (node (ref "LED26") (pin "5") (pinfunction "DP_5") (pintype "passive"))
      (node (ref "LED27") (pin "5") (pinfunction "DP_5") (pintype "passive"))
      (node (ref "LED28") (pin "5") (pinfunction "DP_5") (pintype "passive"))
      (node (ref "LED29") (pin "5") (pinfunction "DP_5") (pintype "passive"))
      (node (ref "LED3") (pin "5") (pinfunction "DP_5") (pintype "passive"))
      (node (ref "LED30") (pin "5") (pinfunction "DP_5") (pintype "passive"))
      (node (ref "LED31") (pin "5") (pinfunction "DP_5") (pintype "passive"))
      (node (ref "LED32") (pin "5") (pinfunction "DP_5") (pintype "passive"))
      (node (ref "LED33") (pin "5") (pinfunction "DP_5") (pintype "passive"))
      (node (ref "LED34") (pin "5") (pinfunction "DP_5") (pintype "passive"))
      (node (ref "LED35") (pin "5") (pinfunction "DP_5") (pintype "passive"))
      (node (ref "LED36") (pin "5") (pinfunction "DP_5") (pintype "passive"))
      (node (ref "LED37") (pin "5") (pinfunction "DP_5") (pintype "passive"))
      (node (ref "LED38") (pin "5") (pinfunction "DP_5") (pintype "passive"))
      (node (ref "LED39") (pin "5") (pinfunction "DP_5") (pintype "passive"))
      (node (ref "LED4") (pin "5") (pinfunction "DP_5") (pintype "passive"))
      (node (ref "LED40") (pin "5") (pinfunction "DP_5") (pintype "passive"))
      (node (ref "LED5") (pin "5") (pinfunction "DP_5") (pintype "passive"))
      (node (ref "LED6") (pin "5") (pinfunction "DP_5") (pintype "passive"))
      (node (ref "LED7") (pin "5") (pinfunction "DP_5") (pintype "passive"))
      (node (ref "LED8") (pin "5") (pinfunction "DP_5") (pintype "passive"))
      (node (ref "LED9") (pin "5") (pinfunction "DP_5") (pintype "passive"))
      (node (ref "T8") (pin "1") (pinfunction "E_1") (pintype "passive"))
    )
    (net (code "19") (name "MR") (class "Default")
      (node (ref "IC1") (pin "10") (pinfunction "SCL_10") (pintype "input"))
      (node (ref "IC2") (pin "10") (pinfunction "SCL_10") (pintype "input"))
      (node (ref "IC3") (pin "10") (pinfunction "SCL_10") (pintype "input"))
      (node (ref "IC4") (pin "10") (pinfunction "SCL_10") (pintype "input"))
      (node (ref "IC5") (pin "10") (pinfunction "SCL_10") (pintype "input"))
      (node (ref "X11") (pin "3") (pinfunction "S_3") (pintype "passive"))
    )
    (net (code "20") (name "Net-(IC1A-QA)") (class "Default")
      (node (ref "IC1") (pin "15") (pinfunction "QA_15") (pintype "tri_state"))
      (node (ref "IC6") (pin "8") (pinfunction "I8_8") (pintype "input"))
    )
    (net (code "21") (name "Net-(IC1A-QB)") (class "Default")
      (node (ref "IC1") (pin "1") (pinfunction "QB_1") (pintype "tri_state"))
      (node (ref "IC6") (pin "7") (pinfunction "I7_7") (pintype "input"))
    )
    (net (code "22") (name "Net-(IC1A-QC)") (class "Default")
      (node (ref "IC1") (pin "2") (pinfunction "QC_2") (pintype "tri_state"))
      (node (ref "IC6") (pin "6") (pinfunction "I6_6") (pintype "input"))
    )
    (net (code "23") (name "Net-(IC1A-QD)") (class "Default")
      (node (ref "IC1") (pin "3") (pinfunction "QD_3") (pintype "tri_state"))
      (node (ref "IC6") (pin "5") (pinfunction "I5_5") (pintype "input"))
    )
    (net (code "24") (name "Net-(IC1A-QE)") (class "Default")
      (node (ref "IC1") (pin "4") (pinfunction "QE_4") (pintype "tri_state"))
      (node (ref "IC6") (pin "4") (pinfunction "I4_4") (pintype "input"))
    )
    (net (code "25") (name "Net-(IC1A-QF)") (class "Default")
      (node (ref "IC1") (pin "5") (pinfunction "QF_5") (pintype "tri_state"))
      (node (ref "IC6") (pin "3") (pinfunction "I3_3") (pintype "input"))
    )
    (net (code "26") (name "Net-(IC1A-QG)") (class "Default")
      (node (ref "IC1") (pin "6") (pinfunction "QG_6") (pintype "tri_state"))
      (node (ref "IC6") (pin "2") (pinfunction "I2_2") (pintype "input"))
    )
    (net (code "27") (name "Net-(IC1A-QH)") (class "Default")
      (node (ref "IC1") (pin "7") (pinfunction "QH_7") (pintype "tri_state"))
      (node (ref "IC6") (pin "1") (pinfunction "I1_1") (pintype "input"))
    )
    (net (code "28") (name "Net-(IC1A-QH*)") (class "Default")
      (node (ref "IC1") (pin "9") (pinfunction "QH*_9") (pintype "tri_state"))
      (node (ref "IC2") (pin "14") (pinfunction "SER_14") (pintype "input"))
    )
    (net (code "29") (name "Net-(IC2A-QA)") (class "Default")
      (node (ref "IC2") (pin "15") (pinfunction "QA_15") (pintype "tri_state"))
      (node (ref "IC7") (pin "8") (pinfunction "I8_8") (pintype "input"))
    )
    (net (code "30") (name "Net-(IC2A-QB)") (class "Default")
      (node (ref "IC2") (pin "1") (pinfunction "QB_1") (pintype "tri_state"))
      (node (ref "IC7") (pin "7") (pinfunction "I7_7") (pintype "input"))
    )
    (net (code "31") (name "Net-(IC2A-QC)") (class "Default")
      (node (ref "IC2") (pin "2") (pinfunction "QC_2") (pintype "tri_state"))
      (node (ref "IC7") (pin "6") (pinfunction "I6_6") (pintype "input"))
    )
    (net (code "32") (name "Net-(IC2A-QD)") (class "Default")
      (node (ref "IC2") (pin "3") (pinfunction "QD_3") (pintype "tri_state"))
      (node (ref "IC7") (pin "5") (pinfunction "I5_5") (pintype "input"))
    )
    (net (code "33") (name "Net-(IC2A-QE)") (class "Default")
      (node (ref "IC2") (pin "4") (pinfunction "QE_4") (pintype "tri_state"))
      (node (ref "IC7") (pin "4") (pinfunction "I4_4") (pintype "input"))
    )
    (net (code "34") (name "Net-(IC2A-QF)") (class "Default")
      (node (ref "IC2") (pin "5") (pinfunction "QF_5") (pintype "tri_state"))
      (node (ref "IC7") (pin "3") (pinfunction "I3_3") (pintype "input"))
    )
    (net (code "35") (name "Net-(IC2A-QG)") (class "Default")
      (node (ref "IC2") (pin "6") (pinfunction "QG_6") (pintype "tri_state"))
      (node (ref "IC7") (pin "2") (pinfunction "I2_2") (pintype "input"))
    )
    (net (code "36") (name "Net-(IC2A-QH)") (class "Default")
      (node (ref "IC2") (pin "7") (pinfunction "QH_7") (pintype "tri_state"))
      (node (ref "IC7") (pin "1") (pinfunction "I1_1") (pintype "input"))
    )
    (net (code "37") (name "Net-(IC2A-QH*)") (class "Default")
      (node (ref "IC2") (pin "9") (pinfunction "QH*_9") (pintype "tri_state"))
      (node (ref "IC3") (pin "14") (pinfunction "SER_14") (pintype "input"))
    )
    (net (code "38") (name "Net-(IC3A-QA)") (class "Default")
      (node (ref "IC3") (pin "15") (pinfunction "QA_15") (pintype "tri_state"))
      (node (ref "IC8") (pin "8") (pinfunction "I8_8") (pintype "input"))
    )
    (net (code "39") (name "Net-(IC3A-QB)") (class "Default")
      (node (ref "IC3") (pin "1") (pinfunction "QB_1") (pintype "tri_state"))
      (node (ref "IC8") (pin "7") (pinfunction "I7_7") (pintype "input"))
    )
    (net (code "40") (name "Net-(IC3A-QC)") (class "Default")
      (node (ref "IC3") (pin "2") (pinfunction "QC_2") (pintype "tri_state"))
      (node (ref "IC8") (pin "6") (pinfunction "I6_6") (pintype "input"))
    )
    (net (code "41") (name "Net-(IC3A-QD)") (class "Default")
      (node (ref "IC3") (pin "3") (pinfunction "QD_3") (pintype "tri_state"))
      (node (ref "IC8") (pin "5") (pinfunction "I5_5") (pintype "input"))
    )
    (net (code "42") (name "Net-(IC3A-QE)") (class "Default")
      (node (ref "IC3") (pin "4") (pinfunction "QE_4") (pintype "tri_state"))
      (node (ref "IC8") (pin "4") (pinfunction "I4_4") (pintype "input"))
    )
    (net (code "43") (name "Net-(IC3A-QF)") (class "Default")
      (node (ref "IC3") (pin "5") (pinfunction "QF_5") (pintype "tri_state"))
      (node (ref "IC8") (pin "3") (pinfunction "I3_3") (pintype "input"))
    )
    (net (code "44") (name "Net-(IC3A-QG)") (class "Default")
      (node (ref "IC3") (pin "6") (pinfunction "QG_6") (pintype "tri_state"))
      (node (ref "IC8") (pin "2") (pinfunction "I2_2") (pintype "input"))
    )
    (net (code "45") (name "Net-(IC3A-QH)") (class "Default")
      (node (ref "IC3") (pin "7") (pinfunction "QH_7") (pintype "tri_state"))
      (node (ref "IC8") (pin "1") (pinfunction "I1_1") (pintype "input"))
    )
    (net (code "46") (name "Net-(IC3A-QH*)") (class "Default")
      (node (ref "IC3") (pin "9") (pinfunction "QH*_9") (pintype "tri_state"))
      (node (ref "IC4") (pin "14") (pinfunction "SER_14") (pintype "input"))
    )
    (net (code "47") (name "Net-(IC4A-QA)") (class "Default")
      (node (ref "IC4") (pin "15") (pinfunction "QA_15") (pintype "tri_state"))
      (node (ref "IC9") (pin "8") (pinfunction "I8_8") (pintype "input"))
    )
    (net (code "48") (name "Net-(IC4A-QB)") (class "Default")
      (node (ref "IC4") (pin "1") (pinfunction "QB_1") (pintype "tri_state"))
      (node (ref "IC9") (pin "7") (pinfunction "I7_7") (pintype "input"))
    )
    (net (code "49") (name "Net-(IC4A-QC)") (class "Default")
      (node (ref "IC4") (pin "2") (pinfunction "QC_2") (pintype "tri_state"))
      (node (ref "IC9") (pin "6") (pinfunction "I6_6") (pintype "input"))
    )
    (net (code "50") (name "Net-(IC4A-QD)") (class "Default")
      (node (ref "IC4") (pin "3") (pinfunction "QD_3") (pintype "tri_state"))
      (node (ref "IC9") (pin "5") (pinfunction "I5_5") (pintype "input"))
    )
    (net (code "51") (name "Net-(IC4A-QE)") (class "Default")
      (node (ref "IC4") (pin "4") (pinfunction "QE_4") (pintype "tri_state"))
      (node (ref "IC9") (pin "4") (pinfunction "I4_4") (pintype "input"))
    )
    (net (code "52") (name "Net-(IC4A-QF)") (class "Default")
      (node (ref "IC4") (pin "5") (pinfunction "QF_5") (pintype "tri_state"))
      (node (ref "IC9") (pin "3") (pinfunction "I3_3") (pintype "input"))
    )
    (net (code "53") (name "Net-(IC4A-QG)") (class "Default")
      (node (ref "IC4") (pin "6") (pinfunction "QG_6") (pintype "tri_state"))
      (node (ref "IC9") (pin "2") (pinfunction "I2_2") (pintype "input"))
    )
    (net (code "54") (name "Net-(IC4A-QH)") (class "Default")
      (node (ref "IC4") (pin "7") (pinfunction "QH_7") (pintype "tri_state"))
      (node (ref "IC9") (pin "1") (pinfunction "I1_1") (pintype "input"))
    )
    (net (code "55") (name "Net-(IC4A-QH*)") (class "Default")
      (node (ref "IC4") (pin "9") (pinfunction "QH*_9") (pintype "tri_state"))
      (node (ref "IC5") (pin "14") (pinfunction "SER_14") (pintype "input"))
    )
    (net (code "56") (name "Net-(IC6-O1)") (class "Default")
      (node (ref "IC6") (pin "18") (pinfunction "O1_18") (pintype "open_collector"))
      (node (ref "X6") (pin "1") (pinfunction "S_1") (pintype "passive"))
    )
    (net (code "57") (name "Net-(IC6-O2)") (class "Default")
      (node (ref "IC6") (pin "17") (pinfunction "O2_17") (pintype "open_collector"))
      (node (ref "X6") (pin "2") (pinfunction "S_2") (pintype "passive"))
    )
    (net (code "58") (name "Net-(IC6-O3)") (class "Default")
      (node (ref "IC6") (pin "16") (pinfunction "O3_16") (pintype "open_collector"))
      (node (ref "X6") (pin "3") (pinfunction "S_3") (pintype "passive"))
    )
    (net (code "59") (name "Net-(IC6-O4)") (class "Default")
      (node (ref "IC6") (pin "15") (pinfunction "O4_15") (pintype "open_collector"))
      (node (ref "X6") (pin "4") (pinfunction "S_4") (pintype "passive"))
    )
    (net (code "60") (name "Net-(IC6-O5)") (class "Default")
      (node (ref "IC6") (pin "14") (pinfunction "O5_14") (pintype "open_collector"))
      (node (ref "X6") (pin "5") (pinfunction "S_5") (pintype "passive"))
    )
    (net (code "61") (name "Net-(IC6-O6)") (class "Default")
      (node (ref "IC6") (pin "13") (pinfunction "O6_13") (pintype "open_collector"))
      (node (ref "X6") (pin "6") (pinfunction "S_6") (pintype "passive"))
    )
    (net (code "62") (name "Net-(IC6-O7)") (class "Default")
      (node (ref "IC6") (pin "12") (pinfunction "O7_12") (pintype "open_collector"))
      (node (ref "X6") (pin "7") (pinfunction "S_7") (pintype "passive"))
    )
    (net (code "63") (name "Net-(IC6-O8)") (class "Default")
      (node (ref "IC6") (pin "11") (pinfunction "O8_11") (pintype "open_collector"))
      (node (ref "X6") (pin "8") (pinfunction "S_8") (pintype "passive"))
    )
    (net (code "64") (name "Net-(IC7-O1)") (class "Default")
      (node (ref "IC7") (pin "18") (pinfunction "O1_18") (pintype "open_collector"))
      (node (ref "X7") (pin "1") (pinfunction "S_1") (pintype "passive"))
    )
    (net (code "65") (name "Net-(IC7-O2)") (class "Default")
      (node (ref "IC7") (pin "17") (pinfunction "O2_17") (pintype "open_collector"))
      (node (ref "X7") (pin "2") (pinfunction "S_2") (pintype "passive"))
    )
    (net (code "66") (name "Net-(IC7-O3)") (class "Default")
      (node (ref "IC7") (pin "16") (pinfunction "O3_16") (pintype "open_collector"))
      (node (ref "X7") (pin "3") (pinfunction "S_3") (pintype "passive"))
    )
    (net (code "67") (name "Net-(IC7-O4)") (class "Default")
      (node (ref "IC7") (pin "15") (pinfunction "O4_15") (pintype "open_collector"))
      (node (ref "X7") (pin "4") (pinfunction "S_4") (pintype "passive"))
    )
    (net (code "68") (name "Net-(IC7-O5)") (class "Default")
      (node (ref "IC7") (pin "14") (pinfunction "O5_14") (pintype "open_collector"))
      (node (ref "X7") (pin "5") (pinfunction "S_5") (pintype "passive"))
    )
    (net (code "69") (name "Net-(IC7-O6)") (class "Default")
      (node (ref "IC7") (pin "13") (pinfunction "O6_13") (pintype "open_collector"))
      (node (ref "X7") (pin "6") (pinfunction "S_6") (pintype "passive"))
    )
    (net (code "70") (name "Net-(IC7-O7)") (class "Default")
      (node (ref "IC7") (pin "12") (pinfunction "O7_12") (pintype "open_collector"))
      (node (ref "X7") (pin "7") (pinfunction "S_7") (pintype "passive"))
    )
    (net (code "71") (name "Net-(IC7-O8)") (class "Default")
      (node (ref "IC7") (pin "11") (pinfunction "O8_11") (pintype "open_collector"))
      (node (ref "X7") (pin "8") (pinfunction "S_8") (pintype "passive"))
    )
    (net (code "72") (name "Net-(IC8-O1)") (class "Default")
      (node (ref "IC8") (pin "18") (pinfunction "O1_18") (pintype "open_collector"))
      (node (ref "X8") (pin "1") (pinfunction "S_1") (pintype "passive"))
    )
    (net (code "73") (name "Net-(IC8-O2)") (class "Default")
      (node (ref "IC8") (pin "17") (pinfunction "O2_17") (pintype "open_collector"))
      (node (ref "X8") (pin "2") (pinfunction "S_2") (pintype "passive"))
    )
    (net (code "74") (name "Net-(IC8-O3)") (class "Default")
      (node (ref "IC8") (pin "16") (pinfunction "O3_16") (pintype "open_collector"))
      (node (ref "X8") (pin "3") (pinfunction "S_3") (pintype "passive"))
    )
    (net (code "75") (name "Net-(IC8-O4)") (class "Default")
      (node (ref "IC8") (pin "15") (pinfunction "O4_15") (pintype "open_collector"))
      (node (ref "X8") (pin "4") (pinfunction "S_4") (pintype "passive"))
    )
    (net (code "76") (name "Net-(IC8-O5)") (class "Default")
      (node (ref "IC8") (pin "14") (pinfunction "O5_14") (pintype "open_collector"))
      (node (ref "X8") (pin "5") (pinfunction "S_5") (pintype "passive"))
    )
    (net (code "77") (name "Net-(IC8-O6)") (class "Default")
      (node (ref "IC8") (pin "13") (pinfunction "O6_13") (pintype "open_collector"))
      (node (ref "X8") (pin "6") (pinfunction "S_6") (pintype "passive"))
    )
    (net (code "78") (name "Net-(IC8-O7)") (class "Default")
      (node (ref "IC8") (pin "12") (pinfunction "O7_12") (pintype "open_collector"))
      (node (ref "X8") (pin "7") (pinfunction "S_7") (pintype "passive"))
    )
    (net (code "79") (name "Net-(IC8-O8)") (class "Default")
      (node (ref "IC8") (pin "11") (pinfunction "O8_11") (pintype "open_collector"))
      (node (ref "X8") (pin "8") (pinfunction "S_8") (pintype "passive"))
    )
    (net (code "80") (name "Net-(IC9-O1)") (class "Default")
      (node (ref "IC9") (pin "18") (pinfunction "O1_18") (pintype "open_collector"))
      (node (ref "X9") (pin "1") (pinfunction "S_1") (pintype "passive"))
    )
    (net (code "81") (name "Net-(IC9-O2)") (class "Default")
      (node (ref "IC9") (pin "17") (pinfunction "O2_17") (pintype "open_collector"))
      (node (ref "X9") (pin "2") (pinfunction "S_2") (pintype "passive"))
    )
    (net (code "82") (name "Net-(IC9-O3)") (class "Default")
      (node (ref "IC9") (pin "16") (pinfunction "O3_16") (pintype "open_collector"))
      (node (ref "X9") (pin "3") (pinfunction "S_3") (pintype "passive"))
    )
    (net (code "83") (name "Net-(IC9-O4)") (class "Default")
      (node (ref "IC9") (pin "15") (pinfunction "O4_15") (pintype "open_collector"))
      (node (ref "X9") (pin "4") (pinfunction "S_4") (pintype "passive"))
    )
    (net (code "84") (name "Net-(IC9-O5)") (class "Default")
      (node (ref "IC9") (pin "14") (pinfunction "O5_14") (pintype "open_collector"))
      (node (ref "X9") (pin "5") (pinfunction "S_5") (pintype "passive"))
    )
    (net (code "85") (name "Net-(IC9-O6)") (class "Default")
      (node (ref "IC9") (pin "13") (pinfunction "O6_13") (pintype "open_collector"))
      (node (ref "X9") (pin "6") (pinfunction "S_6") (pintype "passive"))
    )
    (net (code "86") (name "Net-(IC9-O7)") (class "Default")
      (node (ref "IC9") (pin "12") (pinfunction "O7_12") (pintype "open_collector"))
      (node (ref "X9") (pin "7") (pinfunction "S_7") (pintype "passive"))
    )
    (net (code "87") (name "Net-(IC9-O8)") (class "Default")
      (node (ref "IC9") (pin "11") (pinfunction "O8_11") (pintype "open_collector"))
      (node (ref "X9") (pin "8") (pinfunction "S_8") (pintype "passive"))
    )
    (net (code "88") (name "Net-(IC10-I1)") (class "Default")
      (node (ref "IC10") (pin "1") (pinfunction "I1_1") (pintype "input"))
      (node (ref "IC5") (pin "7") (pinfunction "QH_7") (pintype "tri_state"))
    )
    (net (code "89") (name "Net-(IC10-I2)") (class "Default")
      (node (ref "IC10") (pin "2") (pinfunction "I2_2") (pintype "input"))
      (node (ref "IC5") (pin "6") (pinfunction "QG_6") (pintype "tri_state"))
    )
    (net (code "90") (name "Net-(IC10-I3)") (class "Default")
      (node (ref "IC10") (pin "3") (pinfunction "I3_3") (pintype "input"))
      (node (ref "IC5") (pin "5") (pinfunction "QF_5") (pintype "tri_state"))
    )
    (net (code "91") (name "Net-(IC10-I4)") (class "Default")
      (node (ref "IC10") (pin "4") (pinfunction "I4_4") (pintype "input"))
      (node (ref "IC5") (pin "4") (pinfunction "QE_4") (pintype "tri_state"))
    )
    (net (code "92") (name "Net-(IC10-I5)") (class "Default")
      (node (ref "IC10") (pin "5") (pinfunction "I5_5") (pintype "input"))
      (node (ref "IC5") (pin "3") (pinfunction "QD_3") (pintype "tri_state"))
    )
    (net (code "93") (name "Net-(IC10-I6)") (class "Default")
      (node (ref "IC10") (pin "6") (pinfunction "I6_6") (pintype "input"))
      (node (ref "IC5") (pin "2") (pinfunction "QC_2") (pintype "tri_state"))
    )
    (net (code "94") (name "Net-(IC10-I7)") (class "Default")
      (node (ref "IC10") (pin "7") (pinfunction "I7_7") (pintype "input"))
      (node (ref "IC5") (pin "1") (pinfunction "QB_1") (pintype "tri_state"))
    )
    (net (code "95") (name "Net-(IC10-I8)") (class "Default")
      (node (ref "IC10") (pin "8") (pinfunction "I8_8") (pintype "input"))
      (node (ref "IC5") (pin "15") (pinfunction "QA_15") (pintype "tri_state"))
    )
    (net (code "96") (name "Net-(IC10-O1)") (class "Default")
      (node (ref "IC10") (pin "18") (pinfunction "O1_18") (pintype "open_collector"))
      (node (ref "X10") (pin "1") (pinfunction "S_1") (pintype "passive"))
    )
    (net (code "97") (name "Net-(IC10-O2)") (class "Default")
      (node (ref "IC10") (pin "17") (pinfunction "O2_17") (pintype "open_collector"))
      (node (ref "X10") (pin "2") (pinfunction "S_2") (pintype "passive"))
    )
    (net (code "98") (name "Net-(IC10-O3)") (class "Default")
      (node (ref "IC10") (pin "16") (pinfunction "O3_16") (pintype "open_collector"))
      (node (ref "X10") (pin "3") (pinfunction "S_3") (pintype "passive"))
    )
    (net (code "99") (name "Net-(IC10-O4)") (class "Default")
      (node (ref "IC10") (pin "15") (pinfunction "O4_15") (pintype "open_collector"))
      (node (ref "X10") (pin "4") (pinfunction "S_4") (pintype "passive"))
    )
    (net (code "100") (name "Net-(IC10-O5)") (class "Default")
      (node (ref "IC10") (pin "14") (pinfunction "O5_14") (pintype "open_collector"))
      (node (ref "X10") (pin "5") (pinfunction "S_5") (pintype "passive"))
    )
    (net (code "101") (name "Net-(IC10-O6)") (class "Default")
      (node (ref "IC10") (pin "13") (pinfunction "O6_13") (pintype "open_collector"))
      (node (ref "X10") (pin "6") (pinfunction "S_6") (pintype "passive"))
    )
    (net (code "102") (name "Net-(IC10-O7)") (class "Default")
      (node (ref "IC10") (pin "12") (pinfunction "O7_12") (pintype "open_collector"))
      (node (ref "X10") (pin "7") (pinfunction "S_7") (pintype "passive"))
    )
    (net (code "103") (name "Net-(IC10-O8)") (class "Default")
      (node (ref "IC10") (pin "11") (pinfunction "O8_11") (pintype "open_collector"))
      (node (ref "X10") (pin "8") (pinfunction "S_8") (pintype "passive"))
    )
    (net (code "104") (name "SEG1") (class "Default")
      (node (ref "LED1") (pin "8") (pinfunction "COM_8") (pintype "passive"))
      (node (ref "X2") (pin "10") (pinfunction "S_10") (pintype "passive"))
    )
    (net (code "105") (name "SEG2") (class "Default")
      (node (ref "LED2") (pin "8") (pinfunction "COM_8") (pintype "passive"))
      (node (ref "X2") (pin "9") (pinfunction "S_9") (pintype "passive"))
    )
    (net (code "106") (name "SEG3") (class "Default")
      (node (ref "LED3") (pin "8") (pinfunction "COM_8") (pintype "passive"))
      (node (ref "X2") (pin "8") (pinfunction "S_8") (pintype "passive"))
    )
    (net (code "107") (name "SEG4") (class "Default")
      (node (ref "LED4") (pin "8") (pinfunction "COM_8") (pintype "passive"))
      (node (ref "X2") (pin "7") (pinfunction "S_7") (pintype "passive"))
    )
    (net (code "108") (name "SEG5") (class "Default")
      (node (ref "LED5") (pin "8") (pinfunction "COM_8") (pintype "passive"))
      (node (ref "X2") (pin "6") (pinfunction "S_6") (pintype "passive"))
    )
    (net (code "109") (name "SEG6") (class "Default")
      (node (ref "LED6") (pin "8") (pinfunction "COM_8") (pintype "passive"))
      (node (ref "X2") (pin "5") (pinfunction "S_5") (pintype "passive"))
    )
    (net (code "110") (name "SEG7") (class "Default")
      (node (ref "LED7") (pin "8") (pinfunction "COM_8") (pintype "passive"))
      (node (ref "X2") (pin "4") (pinfunction "S_4") (pintype "passive"))
    )
    (net (code "111") (name "SEG8") (class "Default")
      (node (ref "LED8") (pin "8") (pinfunction "COM_8") (pintype "passive"))
      (node (ref "X2") (pin "3") (pinfunction "S_3") (pintype "passive"))
    )
    (net (code "112") (name "SEG9") (class "Default")
      (node (ref "LED9") (pin "8") (pinfunction "COM_8") (pintype "passive"))
      (node (ref "X2") (pin "2") (pinfunction "S_2") (pintype "passive"))
    )
    (net (code "113") (name "SEG10") (class "Default")
      (node (ref "LED10") (pin "8") (pinfunction "COM_8") (pintype "passive"))
      (node (ref "X2") (pin "1") (pinfunction "S_1") (pintype "passive"))
    )
    (net (code "114") (name "SEG11") (class "Default")
      (node (ref "LED11") (pin "8") (pinfunction "COM_8") (pintype "passive"))
      (node (ref "X3") (pin "10") (pinfunction "S_10") (pintype "passive"))
    )
    (net (code "115") (name "SEG12") (class "Default")
      (node (ref "LED12") (pin "8") (pinfunction "COM_8") (pintype "passive"))
      (node (ref "X3") (pin "9") (pinfunction "S_9") (pintype "passive"))
    )
    (net (code "116") (name "SEG13") (class "Default")
      (node (ref "LED13") (pin "8") (pinfunction "COM_8") (pintype "passive"))
      (node (ref "X3") (pin "8") (pinfunction "S_8") (pintype "passive"))
    )
    (net (code "117") (name "SEG14") (class "Default")
      (node (ref "LED14") (pin "8") (pinfunction "COM_8") (pintype "passive"))
      (node (ref "X3") (pin "7") (pinfunction "S_7") (pintype "passive"))
    )
    (net (code "118") (name "SEG15") (class "Default")
      (node (ref "LED15") (pin "8") (pinfunction "COM_8") (pintype "passive"))
      (node (ref "X3") (pin "6") (pinfunction "S_6") (pintype "passive"))
    )
    (net (code "119") (name "SEG16") (class "Default")
      (node (ref "LED16") (pin "8") (pinfunction "COM_8") (pintype "passive"))
      (node (ref "X3") (pin "5") (pinfunction "S_5") (pintype "passive"))
    )
    (net (code "120") (name "SEG17") (class "Default")
      (node (ref "LED17") (pin "8") (pinfunction "COM_8") (pintype "passive"))
      (node (ref "X3") (pin "4") (pinfunction "S_4") (pintype "passive"))
    )
    (net (code "121") (name "SEG18") (class "Default")
      (node (ref "LED18") (pin "8") (pinfunction "COM_8") (pintype "passive"))
      (node (ref "X3") (pin "3") (pinfunction "S_3") (pintype "passive"))
    )
    (net (code "122") (name "SEG19") (class "Default")
      (node (ref "LED19") (pin "8") (pinfunction "COM_8") (pintype "passive"))
      (node (ref "X3") (pin "2") (pinfunction "S_2") (pintype "passive"))
    )
    (net (code "123") (name "SEG20") (class "Default")
      (node (ref "LED20") (pin "8") (pinfunction "COM_8") (pintype "passive"))
      (node (ref "X3") (pin "1") (pinfunction "S_1") (pintype "passive"))
    )
    (net (code "124") (name "SEG21") (class "Default")
      (node (ref "LED21") (pin "8") (pinfunction "COM_8") (pintype "passive"))
      (node (ref "X4") (pin "10") (pinfunction "S_10") (pintype "passive"))
    )
    (net (code "125") (name "SEG22") (class "Default")
      (node (ref "LED22") (pin "8") (pinfunction "COM_8") (pintype "passive"))
      (node (ref "X4") (pin "9") (pinfunction "S_9") (pintype "passive"))
    )
    (net (code "126") (name "SEG23") (class "Default")
      (node (ref "LED23") (pin "8") (pinfunction "COM_8") (pintype "passive"))
      (node (ref "X4") (pin "8") (pinfunction "S_8") (pintype "passive"))
    )
    (net (code "127") (name "SEG24") (class "Default")
      (node (ref "LED24") (pin "8") (pinfunction "COM_8") (pintype "passive"))
      (node (ref "X4") (pin "7") (pinfunction "S_7") (pintype "passive"))
    )
    (net (code "128") (name "SEG25") (class "Default")
      (node (ref "LED25") (pin "8") (pinfunction "COM_8") (pintype "passive"))
      (node (ref "X4") (pin "6") (pinfunction "S_6") (pintype "passive"))
    )
    (net (code "129") (name "SEG26") (class "Default")
      (node (ref "LED26") (pin "8") (pinfunction "COM_8") (pintype "passive"))
      (node (ref "X4") (pin "5") (pinfunction "S_5") (pintype "passive"))
    )
    (net (code "130") (name "SEG27") (class "Default")
      (node (ref "LED27") (pin "8") (pinfunction "COM_8") (pintype "passive"))
      (node (ref "X4") (pin "4") (pinfunction "S_4") (pintype "passive"))
    )
    (net (code "131") (name "SEG28") (class "Default")
      (node (ref "LED28") (pin "8") (pinfunction "COM_8") (pintype "passive"))
      (node (ref "X4") (pin "3") (pinfunction "S_3") (pintype "passive"))
    )
    (net (code "132") (name "SEG29") (class "Default")
      (node (ref "LED29") (pin "8") (pinfunction "COM_8") (pintype "passive"))
      (node (ref "X4") (pin "2") (pinfunction "S_2") (pintype "passive"))
    )
    (net (code "133") (name "SEG30") (class "Default")
      (node (ref "LED30") (pin "8") (pinfunction "COM_8") (pintype "passive"))
      (node (ref "X4") (pin "1") (pinfunction "S_1") (pintype "passive"))
    )
    (net (code "134") (name "SEG31") (class "Default")
      (node (ref "LED31") (pin "8") (pinfunction "COM_8") (pintype "passive"))
      (node (ref "X5") (pin "10") (pinfunction "S_10") (pintype "passive"))
    )
    (net (code "135") (name "SEG32") (class "Default")
      (node (ref "LED32") (pin "8") (pinfunction "COM_8") (pintype "passive"))
      (node (ref "X5") (pin "9") (pinfunction "S_9") (pintype "passive"))
    )
    (net (code "136") (name "SEG33") (class "Default")
      (node (ref "LED33") (pin "8") (pinfunction "COM_8") (pintype "passive"))
      (node (ref "X5") (pin "8") (pinfunction "S_8") (pintype "passive"))
    )
    (net (code "137") (name "SEG34") (class "Default")
      (node (ref "LED34") (pin "8") (pinfunction "COM_8") (pintype "passive"))
      (node (ref "X5") (pin "7") (pinfunction "S_7") (pintype "passive"))
    )
    (net (code "138") (name "SEG35") (class "Default")
      (node (ref "LED35") (pin "8") (pinfunction "COM_8") (pintype "passive"))
      (node (ref "X5") (pin "6") (pinfunction "S_6") (pintype "passive"))
    )
    (net (code "139") (name "SEG36") (class "Default")
      (node (ref "LED36") (pin "8") (pinfunction "COM_8") (pintype "passive"))
      (node (ref "X5") (pin "5") (pinfunction "S_5") (pintype "passive"))
    )
    (net (code "140") (name "SEG37") (class "Default")
      (node (ref "LED37") (pin "8") (pinfunction "COM_8") (pintype "passive"))
      (node (ref "X5") (pin "4") (pinfunction "S_4") (pintype "passive"))
    )
    (net (code "141") (name "SEG38") (class "Default")
      (node (ref "LED38") (pin "8") (pinfunction "COM_8") (pintype "passive"))
      (node (ref "X5") (pin "3") (pinfunction "S_3") (pintype "passive"))
    )
    (net (code "142") (name "SEG39") (class "Default")
      (node (ref "LED39") (pin "8") (pinfunction "COM_8") (pintype "passive"))
      (node (ref "X5") (pin "2") (pinfunction "S_2") (pintype "passive"))
    )
    (net (code "143") (name "SEG40") (class "Default")
      (node (ref "LED40") (pin "8") (pinfunction "COM_8") (pintype "passive"))
      (node (ref "X5") (pin "1") (pinfunction "S_1") (pintype "passive"))
    )
    (net (code "144") (name "SH_CP") (class "Default")
      (node (ref "IC1") (pin "11") (pinfunction "SCK_11") (pintype "input"))
      (node (ref "IC2") (pin "11") (pinfunction "SCK_11") (pintype "input"))
      (node (ref "IC3") (pin "11") (pinfunction "SCK_11") (pintype "input"))
      (node (ref "IC4") (pin "11") (pinfunction "SCK_11") (pintype "input"))
      (node (ref "IC5") (pin "11") (pinfunction "SCK_11") (pintype "input"))
      (node (ref "X11") (pin "2") (pinfunction "S_2") (pintype "passive"))
    )
    (net (code "145") (name "ST_CP") (class "Default")
      (node (ref "IC1") (pin "12") (pinfunction "RCK_12") (pintype "input"))
      (node (ref "IC2") (pin "12") (pinfunction "RCK_12") (pintype "input"))
      (node (ref "IC3") (pin "12") (pinfunction "RCK_12") (pintype "input"))
      (node (ref "IC4") (pin "12") (pinfunction "RCK_12") (pintype "input"))
      (node (ref "IC5") (pin "12") (pinfunction "RCK_12") (pintype "input"))
      (node (ref "X11") (pin "1") (pinfunction "S_1") (pintype "passive"))
    )
    (net (code "146") (name "VCC") (class "Default")
      (node (ref "IC1") (pin "16") (pinfunction "VCC_16") (pintype "power_in"))
      (node (ref "IC10") (pin "10") (pinfunction "CD+_10") (pintype "passive"))
      (node (ref "IC2") (pin "16") (pinfunction "VCC_16") (pintype "power_in"))
      (node (ref "IC3") (pin "16") (pinfunction "VCC_16") (pintype "power_in"))
      (node (ref "IC4") (pin "16") (pinfunction "VCC_16") (pintype "power_in"))
      (node (ref "IC5") (pin "16") (pinfunction "VCC_16") (pintype "power_in"))
      (node (ref "IC6") (pin "10") (pinfunction "CD+_10") (pintype "passive"))
      (node (ref "IC7") (pin "10") (pinfunction "CD+_10") (pintype "passive"))
      (node (ref "IC8") (pin "10") (pinfunction "CD+_10") (pintype "passive"))
      (node (ref "IC9") (pin "10") (pinfunction "CD+_10") (pintype "passive"))
      (node (ref "T1") (pin "3") (pinfunction "C_3") (pintype "passive"))
      (node (ref "T2") (pin "3") (pinfunction "C_3") (pintype "passive"))
      (node (ref "T3") (pin "3") (pinfunction "C_3") (pintype "passive"))
      (node (ref "T4") (pin "3") (pinfunction "C_3") (pintype "passive"))
      (node (ref "T5") (pin "3") (pinfunction "C_3") (pintype "passive"))
      (node (ref "T6") (pin "3") (pinfunction "C_3") (pintype "passive"))
      (node (ref "T7") (pin "3") (pinfunction "C_3") (pintype "passive"))
      (node (ref "T8") (pin "3") (pinfunction "C_3") (pintype "passive"))
    )
    (net (code "147") (name "unconnected-(IC5A-QH*-Pad9)") (class "Default")
      (node (ref "IC5") (pin "9") (pinfunction "QH*_9") (pintype "tri_state"))
    )
    (net (code "148") (name "unconnected-(LED1-COM-Pad3)") (class "Default")
      (node (ref "LED1") (pin "3") (pinfunction "COM_3") (pintype "passive"))
    )
    (net (code "149") (name "unconnected-(LED2-COM-Pad3)") (class "Default")
      (node (ref "LED2") (pin "3") (pinfunction "COM_3") (pintype "passive"))
    )
    (net (code "150") (name "unconnected-(LED3-COM-Pad3)") (class "Default")
      (node (ref "LED3") (pin "3") (pinfunction "COM_3") (pintype "passive"))
    )
    (net (code "151") (name "unconnected-(LED4-COM-Pad3)") (class "Default")
      (node (ref "LED4") (pin "3") (pinfunction "COM_3") (pintype "passive"))
    )
    (net (code "152") (name "unconnected-(LED5-COM-Pad3)") (class "Default")
      (node (ref "LED5") (pin "3") (pinfunction "COM_3") (pintype "passive"))
    )
    (net (code "153") (name "unconnected-(LED6-COM-Pad3)") (class "Default")
      (node (ref "LED6") (pin "3") (pinfunction "COM_3") (pintype "passive"))
    )
    (net (code "154") (name "unconnected-(LED7-COM-Pad3)") (class "Default")
      (node (ref "LED7") (pin "3") (pinfunction "COM_3") (pintype "passive"))
    )
    (net (code "155") (name "unconnected-(LED8-COM-Pad3)") (class "Default")
      (node (ref "LED8") (pin "3") (pinfunction "COM_3") (pintype "passive"))
    )
    (net (code "156") (name "unconnected-(LED9-COM-Pad3)") (class "Default")
      (node (ref "LED9") (pin "3") (pinfunction "COM_3") (pintype "passive"))
    )
    (net (code "157") (name "unconnected-(LED10-COM-Pad3)") (class "Default")
      (node (ref "LED10") (pin "3") (pinfunction "COM_3") (pintype "passive"))
    )
    (net (code "158") (name "unconnected-(LED11-COM-Pad3)") (class "Default")
      (node (ref "LED11") (pin "3") (pinfunction "COM_3") (pintype "passive"))
    )
    (net (code "159") (name "unconnected-(LED12-COM-Pad3)") (class "Default")
      (node (ref "LED12") (pin "3") (pinfunction "COM_3") (pintype "passive"))
    )
    (net (code "160") (name "unconnected-(LED13-COM-Pad3)") (class "Default")
      (node (ref "LED13") (pin "3") (pinfunction "COM_3") (pintype "passive"))
    )
    (net (code "161") (name "unconnected-(LED14-COM-Pad3)") (class "Default")
      (node (ref "LED14") (pin "3") (pinfunction "COM_3") (pintype "passive"))
    )
    (net (code "162") (name "unconnected-(LED15-COM-Pad3)") (class "Default")
      (node (ref "LED15") (pin "3") (pinfunction "COM_3") (pintype "passive"))
    )
    (net (code "163") (name "unconnected-(LED16-COM-Pad3)") (class "Default")
      (node (ref "LED16") (pin "3") (pinfunction "COM_3") (pintype "passive"))
    )
    (net (code "164") (name "unconnected-(LED17-COM-Pad3)") (class "Default")
      (node (ref "LED17") (pin "3") (pinfunction "COM_3") (pintype "passive"))
    )
    (net (code "165") (name "unconnected-(LED18-COM-Pad3)") (class "Default")
      (node (ref "LED18") (pin "3") (pinfunction "COM_3") (pintype "passive"))
    )
    (net (code "166") (name "unconnected-(LED19-COM-Pad3)") (class "Default")
      (node (ref "LED19") (pin "3") (pinfunction "COM_3") (pintype "passive"))
    )
    (net (code "167") (name "unconnected-(LED20-COM-Pad3)") (class "Default")
      (node (ref "LED20") (pin "3") (pinfunction "COM_3") (pintype "passive"))
    )
    (net (code "168") (name "unconnected-(LED21-COM-Pad3)") (class "Default")
      (node (ref "LED21") (pin "3") (pinfunction "COM_3") (pintype "passive"))
    )
    (net (code "169") (name "unconnected-(LED22-COM-Pad3)") (class "Default")
      (node (ref "LED22") (pin "3") (pinfunction "COM_3") (pintype "passive"))
    )
    (net (code "170") (name "unconnected-(LED23-COM-Pad3)") (class "Default")
      (node (ref "LED23") (pin "3") (pinfunction "COM_3") (pintype "passive"))
    )
    (net (code "171") (name "unconnected-(LED24-COM-Pad3)") (class "Default")
      (node (ref "LED24") (pin "3") (pinfunction "COM_3") (pintype "passive"))
    )
    (net (code "172") (name "unconnected-(LED25-COM-Pad3)") (class "Default")
      (node (ref "LED25") (pin "3") (pinfunction "COM_3") (pintype "passive"))
    )
    (net (code "173") (name "unconnected-(LED26-COM-Pad3)") (class "Default")
      (node (ref "LED26") (pin "3") (pinfunction "COM_3") (pintype "passive"))
    )
    (net (code "174") (name "unconnected-(LED27-COM-Pad3)") (class "Default")
      (node (ref "LED27") (pin "3") (pinfunction "COM_3") (pintype "passive"))
    )
    (net (code "175") (name "unconnected-(LED28-COM-Pad3)") (class "Default")
      (node (ref "LED28") (pin "3") (pinfunction "COM_3") (pintype "passive"))
    )
    (net (code "176") (name "unconnected-(LED29-COM-Pad3)") (class "Default")
      (node (ref "LED29") (pin "3") (pinfunction "COM_3") (pintype "passive"))
    )
    (net (code "177") (name "unconnected-(LED30-COM-Pad3)") (class "Default")
      (node (ref "LED30") (pin "3") (pinfunction "COM_3") (pintype "passive"))
    )
    (net (code "178") (name "unconnected-(LED31-COM-Pad3)") (class "Default")
      (node (ref "LED31") (pin "3") (pinfunction "COM_3") (pintype "passive"))
    )
    (net (code "179") (name "unconnected-(LED32-COM-Pad3)") (class "Default")
      (node (ref "LED32") (pin "3") (pinfunction "COM_3") (pintype "passive"))
    )
    (net (code "180") (name "unconnected-(LED33-COM-Pad3)") (class "Default")
      (node (ref "LED33") (pin "3") (pinfunction "COM_3") (pintype "passive"))
    )
    (net (code "181") (name "unconnected-(LED34-COM-Pad3)") (class "Default")
      (node (ref "LED34") (pin "3") (pinfunction "COM_3") (pintype "passive"))
    )
    (net (code "182") (name "unconnected-(LED35-COM-Pad3)") (class "Default")
      (node (ref "LED35") (pin "3") (pinfunction "COM_3") (pintype "passive"))
    )
    (net (code "183") (name "unconnected-(LED36-COM-Pad3)") (class "Default")
      (node (ref "LED36") (pin "3") (pinfunction "COM_3") (pintype "passive"))
    )
    (net (code "184") (name "unconnected-(LED37-COM-Pad3)") (class "Default")
      (node (ref "LED37") (pin "3") (pinfunction "COM_3") (pintype "passive"))
    )
    (net (code "185") (name "unconnected-(LED38-COM-Pad3)") (class "Default")
      (node (ref "LED38") (pin "3") (pinfunction "COM_3") (pintype "passive"))
    )
    (net (code "186") (name "unconnected-(LED39-COM-Pad3)") (class "Default")
      (node (ref "LED39") (pin "3") (pinfunction "COM_3") (pintype "passive"))
    )
    (net (code "187") (name "unconnected-(LED40-COM-Pad3)") (class "Default")
      (node (ref "LED40") (pin "3") (pinfunction "COM_3") (pintype "passive"))
    )
  )
)
